# xmas_board.net
KiCad netlist of a schematic drawn in EAGLE
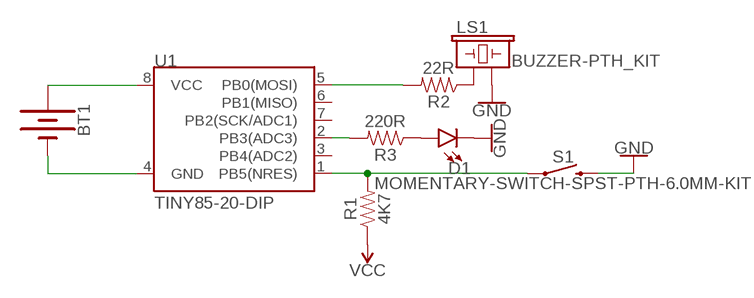
[diagram p0: schematic, sheet 1]

(export (version "E")
  (design (tool "Eeschema 10.0.6"))
  (components
    (comp (ref "BT1")
      (value "BATTERY-20MM_PTH")
      (footprint "eagle-import:BATTCOM_20MM_PTH")
      (libsource (lib "eagle-import") (part "BATTERY-20MM_PTH"))
    )
    (comp (ref "D1")
      (value "LED5MM-KIT")
      (footprint "eagle-import:LED_5MM-KIT")
      (libsource (lib "eagle-import") (part "LED5MM-KIT"))
    )
    (comp (ref "LS1")
      (value "BUZZER-PTH_KIT")
      (footprint "eagle-import:BUZZER-12MM-KIT")
      (libsource (lib "eagle-import") (part "BUZZER-PTH_KIT"))
    )
    (comp (ref "R1")
      (value "4K7")
      (footprint "eagle-import:AXIAL-0.3-KIT")
      (libsource (lib "eagle-import") (part "RESISTORAXIAL-0.3-KIT"))
    )
    (comp (ref "R2")
      (value "22R")
      (footprint "eagle-import:AXIAL-0.3-KIT")
      (libsource (lib "eagle-import") (part "RESISTORAXIAL-0.3-KIT"))
    )
    (comp (ref "R3")
      (value "220R")
      (footprint "eagle-import:AXIAL-0.3-KIT")
      (libsource (lib "eagle-import") (part "RESISTORAXIAL-0.3-KIT"))
    )
    (comp (ref "S1")
      (value "MOMENTARY-SWITCH-SPST-PTH-6.0MM-KIT")
      (footprint "eagle-import:TACTILE_SWITCH_PTH_6.0MM_KIT")
      (libsource (lib "eagle-import") (part "MOMENTARY-SWITCH-SPST-PTH-6.0MM-KIT"))
    )
    (comp (ref "U1")
      (value "TINY85-20-DIP")
      (footprint "eagle-import:DIP08_MCU")
      (libsource (lib "eagle-import") (part "ATTINY45TINY85-20-DIP"))
    )
  )
  (nets
    (net (code "1") (name "GND") (class "Default")
      (node (ref "D1") (pin "K") (pinfunction "C_K") (pintype "passive"))
      (node (ref "LS1") (pin "-") (pinfunction "2_-") (pintype "passive"))
      (node (ref "S1") (pin "3") (pinfunction "2_3") (pintype "passive"))
    )
    (net (code "2") (name "Net-(BT1-+)") (class "Default")
      (node (ref "BT1") (pin "1") (pinfunction "+_1") (pintype "power_in"))
      (node (ref "U1") (pin "8") (pinfunction "VCC_8") (pintype "bidirectional"))
    )
    (net (code "3") (name "Net-(BT1--)") (class "Default")
      (node (ref "BT1") (pin "2") (pinfunction "-_2") (pintype "power_in"))
      (node (ref "U1") (pin "4") (pinfunction "GND_4") (pintype "bidirectional"))
    )
    (net (code "4") (name "Net-(LS1-1)") (class "Default")
      (node (ref "LS1") (pin "+") (pinfunction "1_+") (pintype "passive"))
      (node (ref "R2") (pin "P$1") (pinfunction "1_P$1") (pintype "passive"))
    )
    (net (code "5") (name "Net-(R1-2)") (class "Default")
      (node (ref "R1") (pin "P$2") (pinfunction "2_P$2") (pintype "passive"))
      (node (ref "S1") (pin "1") (pinfunction "1_1") (pintype "passive"))
      (node (ref "U1") (pin "1") (pinfunction "PB5(NRES)_1") (pintype "bidirectional"))
    )
    (net (code "6") (name "Net-(R2-2)") (class "Default")
      (node (ref "R2") (pin "P$2") (pinfunction "2_P$2") (pintype "passive"))
      (node (ref "U1") (pin "5") (pinfunction "PB0(MOSI)_5") (pintype "bidirectional"))
    )
    (net (code "7") (name "Net-(R3-1)") (class "Default")
      (node (ref "D1") (pin "A") (pinfunction "A_A") (pintype "passive"))
      (node (ref "R3") (pin "P$1") (pinfunction "1_P$1") (pintype "passive"))
    )
    (net (code "8") (name "Net-(R3-2)") (class "Default")
      (node (ref "R3") (pin "P$2") (pinfunction "2_P$2") (pintype "passive"))
      (node (ref "U1") (pin "2") (pinfunction "PB3(ADC3)_2") (pintype "bidirectional"))
    )
    (net (code "9") (name "VCC") (class "Default")
      (node (ref "R1") (pin "P$1") (pinfunction "1_P$1") (pintype "passive"))
    )
    (net (code "10") (name "unconnected-(U1-PB1(MISO)-Pad6)") (class "Default")
      (node (ref "U1") (pin "6") (pinfunction "PB1(MISO)_6") (pintype "bidirectional"))
    )
    (net (code "11") (name "unconnected-(U1-PB2(SCK{slash}ADC1)-Pad7)") (class "Default")
      (node (ref "U1") (pin "7") (pinfunction "PB2(SCK/ADC1)_7") (pintype "bidirectional"))
    )
    (net (code "12") (name "unconnected-(U1-PB4(ADC2)-Pad3)") (class "Default")
      (node (ref "U1") (pin "3") (pinfunction "PB4(ADC2)_3") (pintype "bidirectional"))
    )
  )
)
